# PowerPlane.net
KiCad netlist of a schematic drawn in Altium Designer
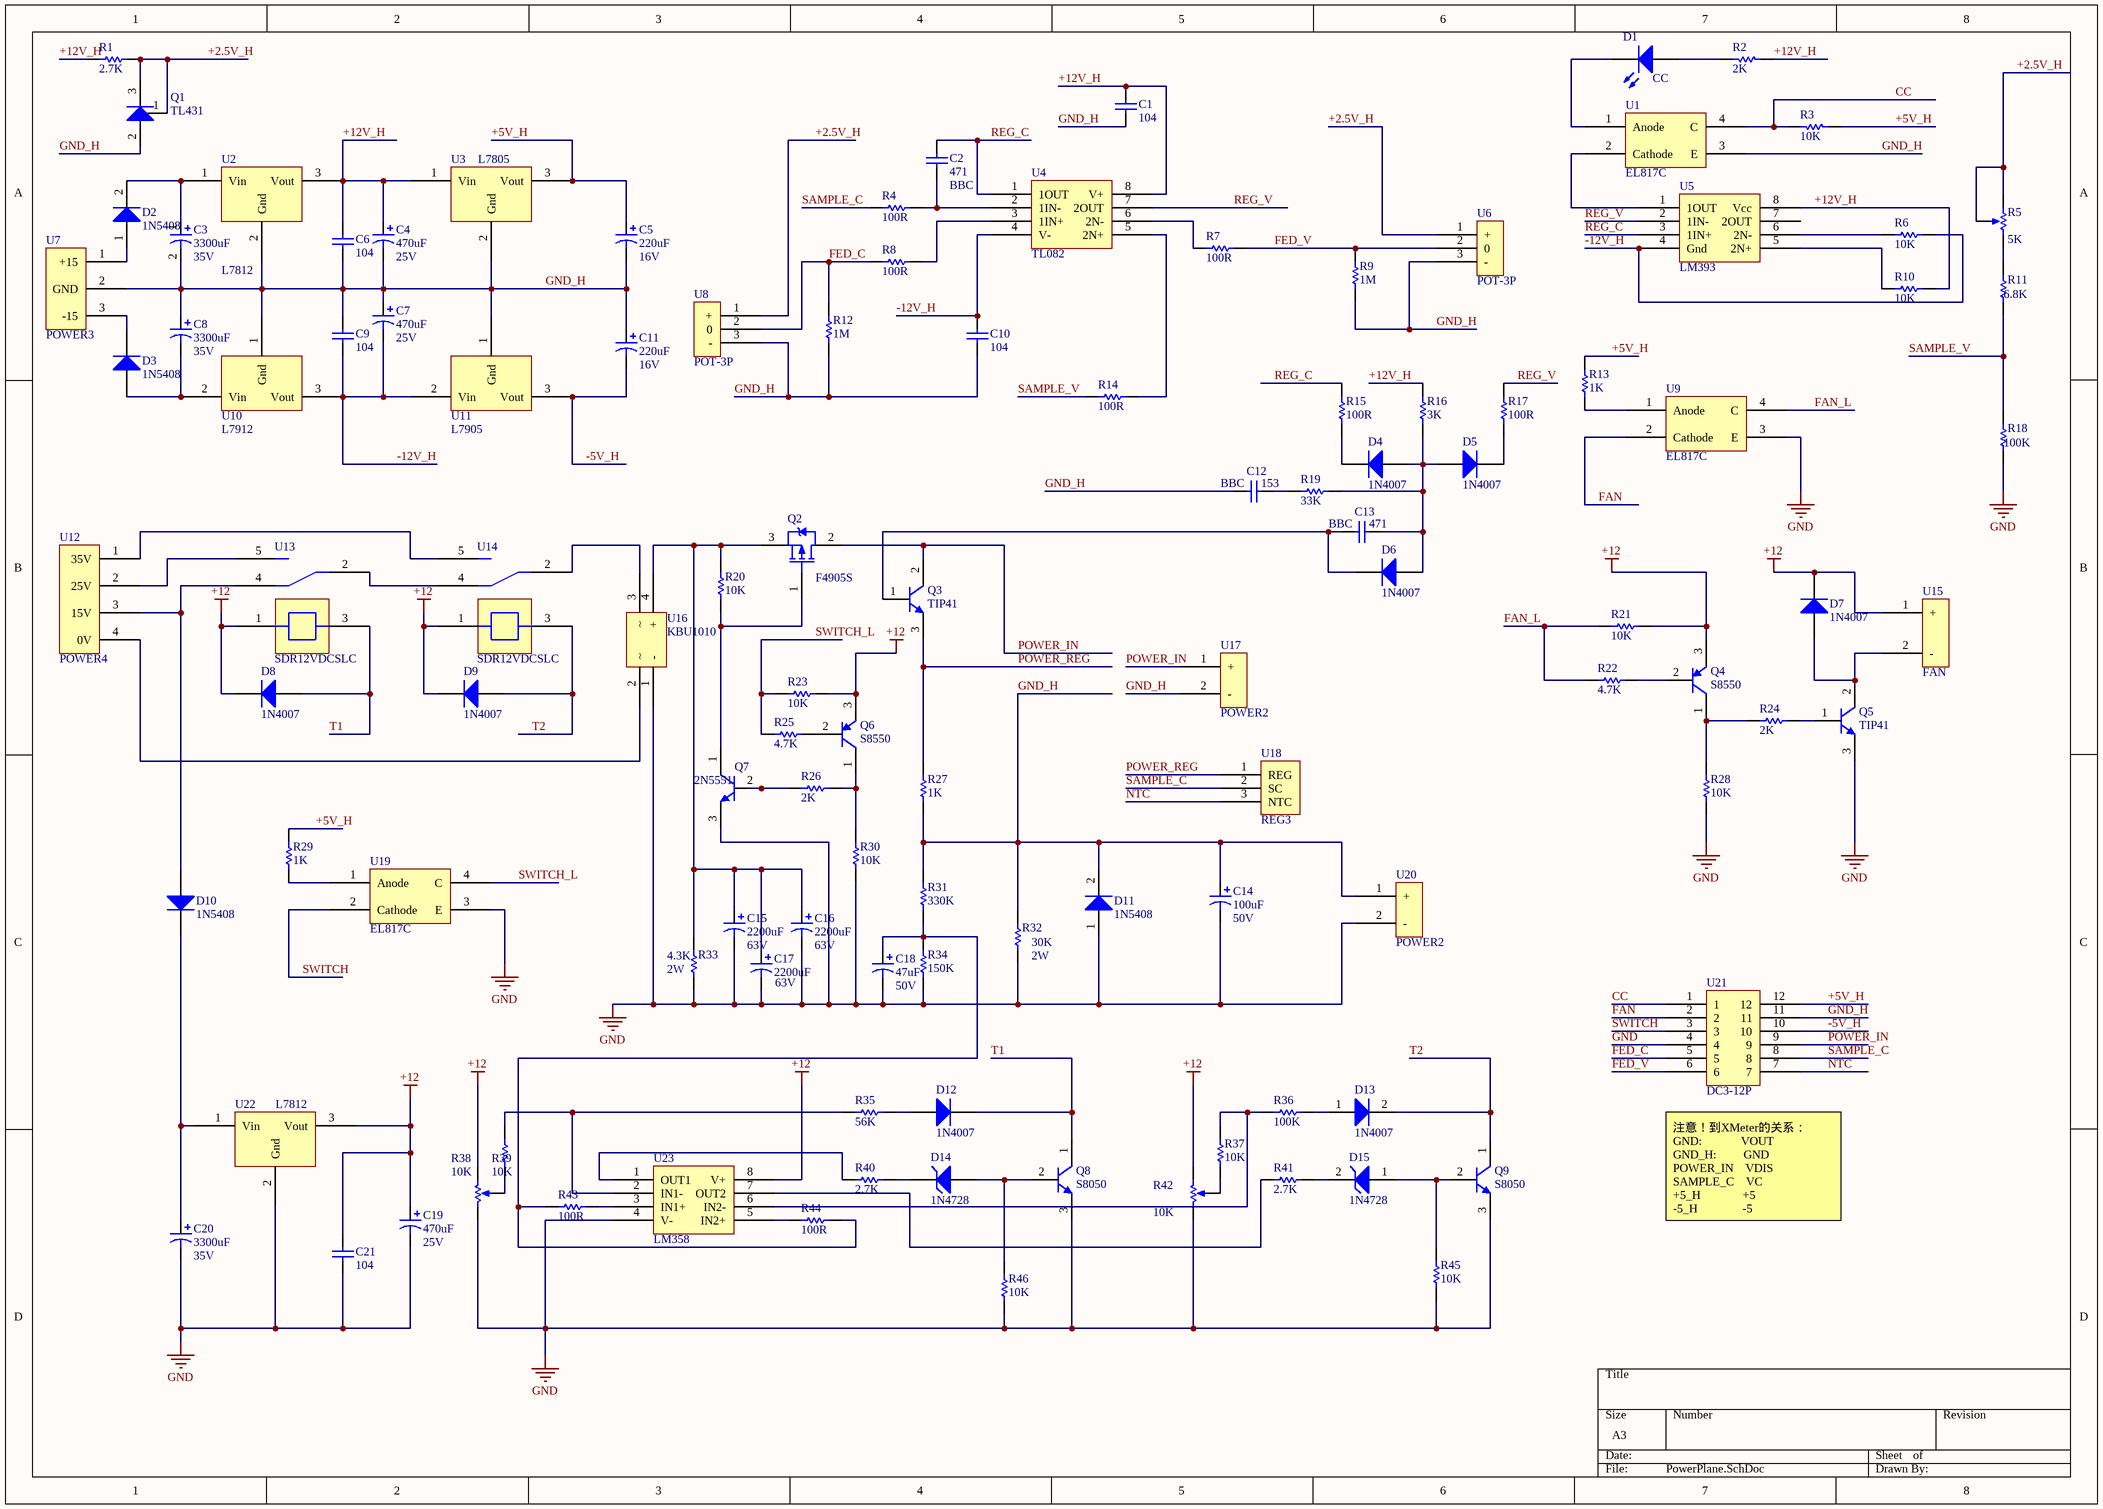
[diagram p0: PowerPlane.SchDoc]

(export (version "E")
  (design (tool "Eeschema 10.0.6"))
  (components
    (comp (ref "C1")
      (value "104")
      (footprint "CNCPowerSupply:RAD-0.2")
      (description "Capacitor")
      (fields (field (name "PUBLISHER") "Altium Limited"))
      (libsource (lib "Miscellaneous Devices") (part "Cap"))
    )
    (comp (ref "C2")
      (value "BBC")
      (footprint "CNCPowerSupply:RAD-0.2")
      (description "Capacitor")
      (fields (field (name "ALTIUM_VALUE") "471") (field (name "PUBLISHER") "Altium Limited"))
      (libsource (lib "Miscellaneous Devices") (part "Cap"))
    )
    (comp (ref "C3")
      (value "35V")
      (footprint "CNCPowerSupply:CAPPR7.5-16x25")
      (description "Polarized Capacitor (Radial)")
      (fields (field (name "ALTIUM_VALUE") "3300uF") (field (name "PUBLISHER") "Altium Limited"))
      (libsource (lib "Miscellaneous Devices") (part "Cap Pol1"))
    )
    (comp (ref "C4")
      (value "25V")
      (footprint "CNCPowerSupply:CAPPR5-8x12")
      (description "Polarized Capacitor (Radial)")
      (fields (field (name "ALTIUM_VALUE") "470uF") (field (name "PUBLISHER") "Altium Limited"))
      (libsource (lib "") (part "Cap Pol1_1"))
    )
    (comp (ref "C5")
      (value "16V")
      (footprint "CNCPowerSupply:CAPPR5-6.3x11")
      (description "Polarized Capacitor (Radial)")
      (fields (field (name "ALTIUM_VALUE") "220uF") (field (name "PUBLISHER") "Altium Limited"))
      (libsource (lib "") (part "Cap Pol1_1"))
    )
    (comp (ref "C6")
      (value "104")
      (footprint "CNCPowerSupply:RAD-0.2")
      (description "Capacitor")
      (fields (field (name "PUBLISHER") "Altium Limited"))
      (libsource (lib "Miscellaneous Devices") (part "Cap"))
    )
    (comp (ref "C7")
      (value "25V")
      (footprint "CNCPowerSupply:CAPPR5-8x12")
      (description "Polarized Capacitor (Radial)")
      (fields (field (name "ALTIUM_VALUE") "470uF") (field (name "PUBLISHER") "Altium Limited"))
      (libsource (lib "") (part "Cap Pol1_1"))
    )
    (comp (ref "C8")
      (value "35V")
      (footprint "CNCPowerSupply:CAPPR7.5-16x25")
      (description "Polarized Capacitor (Radial)")
      (fields (field (name "ALTIUM_VALUE") "3300uF") (field (name "PUBLISHER") "Altium Limited"))
      (libsource (lib "") (part "Cap Pol1_1"))
    )
    (comp (ref "C9")
      (value "104")
      (footprint "CNCPowerSupply:RAD-0.2")
      (description "Capacitor")
      (fields (field (name "PUBLISHER") "Altium Limited"))
      (libsource (lib "Miscellaneous Devices") (part "Cap"))
    )
    (comp (ref "C10")
      (value "104")
      (footprint "CNCPowerSupply:RAD-0.2")
      (description "Capacitor")
      (fields (field (name "PUBLISHER") "Altium Limited"))
      (libsource (lib "Miscellaneous Devices") (part "Cap"))
    )
    (comp (ref "C11")
      (value "16V")
      (footprint "CNCPowerSupply:CAPPR5-6.3x11")
      (description "Polarized Capacitor (Radial)")
      (fields (field (name "ALTIUM_VALUE") "220uF") (field (name "PUBLISHER") "Altium Limited"))
      (libsource (lib "") (part "Cap Pol1_1"))
    )
    (comp (ref "C12")
      (value "BBC")
      (footprint "CNCPowerSupply:RAD-0.4-BBC")
      (description "Capacitor")
      (fields (field (name "ALTIUM_VALUE") "153") (field (name "PUBLISHER") "Altium Limited"))
      (libsource (lib "Miscellaneous Devices") (part "Cap"))
    )
    (comp (ref "C13")
      (value "BBC")
      (footprint "CNCPowerSupply:RAD-0.2")
      (description "Capacitor")
      (fields (field (name "ALTIUM_VALUE") "471") (field (name "PUBLISHER") "Altium Limited"))
      (libsource (lib "Miscellaneous Devices") (part "Cap"))
    )
    (comp (ref "C14")
      (value "50V")
      (footprint "CNCPowerSupply:CAPPR5-8x12")
      (description "Polarized Capacitor (Radial)")
      (fields (field (name "ALTIUM_VALUE") "100uF") (field (name "PUBLISHER") "Altium Limited"))
      (libsource (lib "") (part "Cap Pol1_1"))
    )
    (comp (ref "C15")
      (value "63V")
      (footprint "CNCPowerSupply:CAPPR7.5-18x35.5")
      (description "Polarized Capacitor (Radial)")
      (fields (field (name "ALTIUM_VALUE") "2200uF") (field (name "PUBLISHER") "Altium Limited"))
      (libsource (lib "") (part "Cap Pol1_1"))
    )
    (comp (ref "C16")
      (value "63V")
      (footprint "CNCPowerSupply:CAPPR7.5-18x35.5")
      (description "Polarized Capacitor (Radial)")
      (fields (field (name "ALTIUM_VALUE") "2200uF") (field (name "PUBLISHER") "Altium Limited"))
      (libsource (lib "") (part "Cap Pol1_1"))
    )
    (comp (ref "C17")
      (value "63V")
      (footprint "CNCPowerSupply:CAPPR7.5-18x35.5")
      (description "Polarized Capacitor (Radial)")
      (fields (field (name "ALTIUM_VALUE") "2200uF") (field (name "PUBLISHER") "Altium Limited"))
      (libsource (lib "") (part "Cap Pol1_1"))
    )
    (comp (ref "C18")
      (value "50V")
      (footprint "CNCPowerSupply:CAPPR5-6.3x15")
      (description "Polarized Capacitor (Radial)")
      (fields (field (name "ALTIUM_VALUE") "47uF") (field (name "PUBLISHER") "Altium Limited"))
      (libsource (lib "") (part "Cap Pol1_1"))
    )
    (comp (ref "C19")
      (value "25V")
      (footprint "CNCPowerSupply:CAPPR5-8x12")
      (description "Polarized Capacitor (Radial)")
      (fields (field (name "ALTIUM_VALUE") "470uF") (field (name "PUBLISHER") "Altium Limited"))
      (libsource (lib "") (part "Cap Pol1_1"))
    )
    (comp (ref "C20")
      (value "35V")
      (footprint "CNCPowerSupply:CAPPR7.5-16x25")
      (description "Polarized Capacitor (Radial)")
      (fields (field (name "ALTIUM_VALUE") "3300uF") (field (name "PUBLISHER") "Altium Limited"))
      (libsource (lib "") (part "Cap Pol1_1"))
    )
    (comp (ref "C21")
      (value "104")
      (footprint "CNCPowerSupply:RAD-0.2")
      (description "Capacitor")
      (fields (field (name "PUBLISHER") "Altium Limited"))
      (libsource (lib "Miscellaneous Devices") (part "Cap"))
    )
    (comp (ref "D1")
      (value "CC")
      (footprint "CNCPowerSupply:LED")
      (description "Typical RED GaAs LED")
      (fields (field (name "PUBLISHER") "Altium Limited"))
      (libsource (lib "Miscellaneous Devices") (part "LED1"))
    )
    (comp (ref "D2")
      (value "1N5408")
      (footprint "CNCPowerSupply:DIO18.84-9.6x5.6-Vetical")
      (description "1 Amp General Purpose Rectifier")
      (fields (field (name "PUBLISHER") "Altium Limited"))
      (libsource (lib "Miscellaneous Devices") (part "Diode 1N4007"))
    )
    (comp (ref "D3")
      (value "1N5408")
      (footprint "CNCPowerSupply:DIO18.84-9.6x5.6-Vetical")
      (description "1 Amp General Purpose Rectifier")
      (fields (field (name "PUBLISHER") "Altium Limited"))
      (libsource (lib "") (part "Diode 1N4007_1"))
    )
    (comp (ref "D4")
      (value "1N4007")
      (footprint "CNCPowerSupply:DO-41")
      (description "1 Amp General Purpose Rectifier")
      (fields (field (name "PUBLISHER") "Altium Limited"))
      (libsource (lib "") (part "Diode 1N4007_1"))
    )
    (comp (ref "D5")
      (value "1N4007")
      (footprint "CNCPowerSupply:DO-41")
      (description "1 Amp General Purpose Rectifier")
      (fields (field (name "PUBLISHER") "Altium Limited"))
      (libsource (lib "") (part "Diode 1N4007_1"))
    )
    (comp (ref "D6")
      (value "1N4007")
      (footprint "CNCPowerSupply:DO-41")
      (description "1 Amp General Purpose Rectifier")
      (fields (field (name "PUBLISHER") "Altium Limited"))
      (libsource (lib "") (part "Diode 1N4007_1"))
    )
    (comp (ref "D7")
      (value "1N4007")
      (footprint "CNCPowerSupply:DO-41")
      (description "1 Amp General Purpose Rectifier")
      (fields (field (name "PUBLISHER") "Altium Limited"))
      (libsource (lib "") (part "Diode 1N4007_1"))
    )
    (comp (ref "D8")
      (value "1N4007")
      (footprint "CNCPowerSupply:DO-41")
      (description "1 Amp General Purpose Rectifier")
      (fields (field (name "PUBLISHER") "Altium Limited"))
      (libsource (lib "") (part "Diode 1N4007_1"))
    )
    (comp (ref "D9")
      (value "1N4007")
      (footprint "CNCPowerSupply:DO-41")
      (description "1 Amp General Purpose Rectifier")
      (fields (field (name "PUBLISHER") "Altium Limited"))
      (libsource (lib "") (part "Diode 1N4007_1"))
    )
    (comp (ref "D10")
      (value "1N5408")
      (footprint "CNCPowerSupply:DIO18.84-9.6x5.6-Vetical")
      (description "1 Amp General Purpose Rectifier")
      (fields (field (name "PUBLISHER") "Altium Limited"))
      (libsource (lib "") (part "Diode 1N4007_1"))
    )
    (comp (ref "D11")
      (value "1N5408")
      (footprint "CNCPowerSupply:DIO18.84-9.6x5.6-Vetical")
      (description "1 Amp General Purpose Rectifier")
      (fields (field (name "PUBLISHER") "Altium Limited"))
      (libsource (lib "Miscellaneous Devices") (part "Diode 1N4007"))
    )
    (comp (ref "D12")
      (value "1N4007")
      (footprint "CNCPowerSupply:DO-41")
      (description "1 Amp General Purpose Rectifier")
      (fields (field (name "PUBLISHER") "Altium Limited"))
      (libsource (lib "") (part "Diode 1N4007_1"))
    )
    (comp (ref "D13")
      (value "1N4007")
      (footprint "CNCPowerSupply:DO-41")
      (description "1 Amp General Purpose Rectifier")
      (fields (field (name "PUBLISHER") "Altium Limited"))
      (libsource (lib "Miscellaneous Devices") (part "Diode 1N4007"))
    )
    (comp (ref "D14")
      (value "1N4728")
      (footprint "CNCPowerSupply:DO-41")
      (description "Zener Diode")
      (fields (field (name "PUBLISHER") "Altium Limited"))
      (libsource (lib "") (part "D Zener_1"))
    )
    (comp (ref "D15")
      (value "1N4728")
      (footprint "CNCPowerSupply:DO-41")
      (description "Zener Diode")
      (fields (field (name "PUBLISHER") "Altium Limited"))
      (libsource (lib "Miscellaneous Devices") (part "D Zener"))
    )
    (comp (ref "Q1")
      (value "TL431")
      (footprint "CNCPowerSupply:TO-226-AA")
      (libsource (lib "CNCPowerSupply") (part "TL431"))
    )
    (comp (ref "Q2")
      (value "F4905S")
      (footprint "CNCPowerSupply:D2-PAK")
      (description "P-Channel Power MOSFET")
      (fields (field (name "PUBLISHER") "Altium Limited"))
      (libsource (lib "Miscellaneous Devices") (part "PMOS-2"))
    )
    (comp (ref "Q3")
      (value "TIP41")
      (footprint "CNCPowerSupply:TO-220AB - HEATSINK")
      (description "NPN Bipolar Transistor")
      (fields (field (name "PUBLISHER") "Altium Limited"))
      (libsource (lib "") (part "NPN_1"))
    )
    (comp (ref "Q4")
      (value "S8550")
      (footprint "CNCPowerSupply:TO-92A")
      (description "PNP Bipolar Transistor")
      (fields (field (name "PUBLISHER") "Altium Limited"))
      (libsource (lib "Miscellaneous Devices") (part "PNP"))
    )
    (comp (ref "Q5")
      (value "TIP41")
      (footprint "CNCPowerSupply:TO-220AB")
      (description "NPN Bipolar Transistor")
      (fields (field (name "PUBLISHER") "Altium Limited"))
      (libsource (lib "") (part "NPN_1"))
    )
    (comp (ref "Q6")
      (value "S8550")
      (footprint "CNCPowerSupply:TO-92A")
      (description "PNP Bipolar Transistor")
      (fields (field (name "PUBLISHER") "Altium Limited"))
      (libsource (lib "Miscellaneous Devices") (part "PNP"))
    )
    (comp (ref "Q7")
      (value "2N5551")
      (footprint "CNCPowerSupply:TO-92A")
      (description "NPN Bipolar Transistor")
      (fields (field (name "PUBLISHER") "Altium Limited"))
      (libsource (lib "Miscellaneous Devices") (part "NPN"))
    )
    (comp (ref "Q8")
      (value "S8050")
      (footprint "CNCPowerSupply:TO-92A")
      (description "NPN Bipolar Transistor")
      (fields (field (name "PUBLISHER") "Altium Limited"))
      (libsource (lib "Miscellaneous Devices") (part "NPN"))
    )
    (comp (ref "Q9")
      (value "S8050")
      (footprint "CNCPowerSupply:TO-92A")
      (description "NPN Bipolar Transistor")
      (fields (field (name "PUBLISHER") "Altium Limited"))
      (libsource (lib "Miscellaneous Devices") (part "NPN"))
    )
    (comp (ref "R1")
      (value "2.7K")
      (footprint "CNCPowerSupply:AXIAL-0.3")
      (description "Resistor")
      (fields (field (name "PUBLISHER") "Altium Limited"))
      (libsource (lib "Miscellaneous Devices") (part "Res1"))
    )
    (comp (ref "R2")
      (value "2K")
      (footprint "CNCPowerSupply:AXIAL-0.3")
      (description "Resistor")
      (fields (field (name "PUBLISHER") "Altium Limited"))
      (libsource (lib "Miscellaneous Devices") (part "Res1"))
    )
    (comp (ref "R3")
      (value "10K")
      (footprint "CNCPowerSupply:AXIAL-0.3")
      (description "Resistor")
      (fields (field (name "PUBLISHER") "Altium Limited"))
      (libsource (lib "Miscellaneous Devices") (part "Res1"))
    )
    (comp (ref "R4")
      (value "100R")
      (footprint "CNCPowerSupply:AXIAL-0.3")
      (description "Resistor")
      (fields (field (name "PUBLISHER") "Altium Limited"))
      (libsource (lib "Miscellaneous Devices") (part "Res1"))
    )
    (comp (ref "R5")
      (value "5K")
      (footprint "CNCPowerSupply:VR5")
      (description "Potentiometer")
      (fields (field (name "PUBLISHER") "Altium Limited"))
      (libsource (lib "Miscellaneous Devices") (part "RPot"))
    )
    (comp (ref "R6")
      (value "10K")
      (footprint "CNCPowerSupply:AXIAL-0.3")
      (description "Resistor")
      (fields (field (name "PUBLISHER") "Altium Limited"))
      (libsource (lib "Miscellaneous Devices") (part "Res1"))
    )
    (comp (ref "R7")
      (value "100R")
      (footprint "CNCPowerSupply:AXIAL-0.3")
      (description "Resistor")
      (fields (field (name "PUBLISHER") "Altium Limited"))
      (libsource (lib "Miscellaneous Devices") (part "Res1"))
    )
    (comp (ref "R8")
      (value "100R")
      (footprint "CNCPowerSupply:AXIAL-0.3")
      (description "Resistor")
      (fields (field (name "PUBLISHER") "Altium Limited"))
      (libsource (lib "Miscellaneous Devices") (part "Res1"))
    )
    (comp (ref "R9")
      (value "1M")
      (footprint "CNCPowerSupply:AXIAL-0.3")
      (description "Resistor")
      (fields (field (name "PUBLISHER") "Altium Limited"))
      (libsource (lib "Miscellaneous Devices") (part "Res1"))
    )
    (comp (ref "R10")
      (value "10K")
      (footprint "CNCPowerSupply:AXIAL-0.3")
      (description "Resistor")
      (fields (field (name "PUBLISHER") "Altium Limited"))
      (libsource (lib "Miscellaneous Devices") (part "Res1"))
    )
    (comp (ref "R11")
      (value "6.8K")
      (footprint "CNCPowerSupply:AXIAL-0.3")
      (description "Resistor")
      (fields (field (name "PUBLISHER") "Altium Limited"))
      (libsource (lib "Miscellaneous Devices") (part "Res1"))
    )
    (comp (ref "R12")
      (value "1M")
      (footprint "CNCPowerSupply:AXIAL-0.3")
      (description "Resistor")
      (fields (field (name "PUBLISHER") "Altium Limited"))
      (libsource (lib "Miscellaneous Devices") (part "Res1"))
    )
    (comp (ref "R13")
      (value "1K")
      (footprint "CNCPowerSupply:AXIAL-0.3")
      (description "Resistor")
      (fields (field (name "PUBLISHER") "Altium Limited"))
      (libsource (lib "Miscellaneous Devices") (part "Res1"))
    )
    (comp (ref "R14")
      (value "100R")
      (footprint "CNCPowerSupply:AXIAL-0.3")
      (description "Resistor")
      (fields (field (name "PUBLISHER") "Altium Limited"))
      (libsource (lib "Miscellaneous Devices") (part "Res1"))
    )
    (comp (ref "R15")
      (value "100R")
      (footprint "CNCPowerSupply:AXIAL-0.3")
      (description "Resistor")
      (fields (field (name "PUBLISHER") "Altium Limited"))
      (libsource (lib "Miscellaneous Devices") (part "Res1"))
    )
    (comp (ref "R16")
      (value "3K")
      (footprint "CNCPowerSupply:AXIAL-0.3")
      (description "Resistor")
      (fields (field (name "PUBLISHER") "Altium Limited"))
      (libsource (lib "Miscellaneous Devices") (part "Res1"))
    )
    (comp (ref "R17")
      (value "100R")
      (footprint "CNCPowerSupply:AXIAL-0.3")
      (description "Resistor")
      (fields (field (name "PUBLISHER") "Altium Limited"))
      (libsource (lib "Miscellaneous Devices") (part "Res1"))
    )
    (comp (ref "R18")
      (value "100K")
      (footprint "CNCPowerSupply:AXIAL-0.3")
      (description "Resistor")
      (fields (field (name "PUBLISHER") "Altium Limited"))
      (libsource (lib "Miscellaneous Devices") (part "Res1"))
    )
    (comp (ref "R19")
      (value "33K")
      (footprint "CNCPowerSupply:AXIAL-0.3")
      (description "Resistor")
      (fields (field (name "PUBLISHER") "Altium Limited"))
      (libsource (lib "Miscellaneous Devices") (part "Res1"))
    )
    (comp (ref "R20")
      (value "10K")
      (footprint "CNCPowerSupply:AXIAL-0.3")
      (description "Resistor")
      (fields (field (name "PUBLISHER") "Altium Limited"))
      (libsource (lib "Miscellaneous Devices") (part "Res1"))
    )
    (comp (ref "R21")
      (value "10K")
      (footprint "CNCPowerSupply:AXIAL-0.3")
      (description "Resistor")
      (fields (field (name "PUBLISHER") "Altium Limited"))
      (libsource (lib "Miscellaneous Devices") (part "Res1"))
    )
    (comp (ref "R22")
      (value "4.7K")
      (footprint "CNCPowerSupply:AXIAL-0.3")
      (description "Resistor")
      (fields (field (name "PUBLISHER") "Altium Limited"))
      (libsource (lib "Miscellaneous Devices") (part "Res1"))
    )
    (comp (ref "R23")
      (value "10K")
      (footprint "CNCPowerSupply:AXIAL-0.3")
      (description "Resistor")
      (fields (field (name "PUBLISHER") "Altium Limited"))
      (libsource (lib "Miscellaneous Devices") (part "Res1"))
    )
    (comp (ref "R24")
      (value "2K")
      (footprint "CNCPowerSupply:AXIAL-0.3")
      (description "Resistor")
      (fields (field (name "PUBLISHER") "Altium Limited"))
      (libsource (lib "Miscellaneous Devices") (part "Res1"))
    )
    (comp (ref "R25")
      (value "4.7K")
      (footprint "CNCPowerSupply:AXIAL-0.3")
      (description "Resistor")
      (fields (field (name "PUBLISHER") "Altium Limited"))
      (libsource (lib "Miscellaneous Devices") (part "Res1"))
    )
    (comp (ref "R26")
      (value "2K")
      (footprint "CNCPowerSupply:AXIAL-0.3")
      (description "Resistor")
      (fields (field (name "PUBLISHER") "Altium Limited"))
      (libsource (lib "Miscellaneous Devices") (part "Res1"))
    )
    (comp (ref "R27")
      (value "1K")
      (footprint "CNCPowerSupply:AXIAL-0.3")
      (description "Resistor")
      (fields (field (name "PUBLISHER") "Altium Limited"))
      (libsource (lib "Miscellaneous Devices") (part "Res1"))
    )
    (comp (ref "R28")
      (value "10K")
      (footprint "CNCPowerSupply:AXIAL-0.3")
      (description "Resistor")
      (fields (field (name "PUBLISHER") "Altium Limited"))
      (libsource (lib "Miscellaneous Devices") (part "Res1"))
    )
    (comp (ref "R29")
      (value "1K")
      (footprint "CNCPowerSupply:AXIAL-0.3")
      (description "Resistor")
      (fields (field (name "PUBLISHER") "Altium Limited"))
      (libsource (lib "Miscellaneous Devices") (part "Res1"))
    )
    (comp (ref "R30")
      (value "10K")
      (footprint "CNCPowerSupply:AXIAL-0.3")
      (description "Resistor")
      (fields (field (name "PUBLISHER") "Altium Limited"))
      (libsource (lib "Miscellaneous Devices") (part "Res1"))
    )
    (comp (ref "R31")
      (value "330K")
      (footprint "CNCPowerSupply:AXIAL-0.3")
      (description "Resistor")
      (fields (field (name "PUBLISHER") "Altium Limited"))
      (libsource (lib "Miscellaneous Devices") (part "Res1"))
    )
    (comp (ref "R32")
      (value "2W")
      (footprint "CNCPowerSupply:AXIAL-0.7")
      (description "Resistor")
      (fields (field (name "ALTIUM_VALUE") "30K") (field (name "PUBLISHER") "Altium Limited"))
      (libsource (lib "Miscellaneous Devices") (part "Res1"))
    )
    (comp (ref "R33")
      (value "2W")
      (footprint "CNCPowerSupply:AXIAL-0.7")
      (description "Resistor")
      (fields (field (name "ALTIUM_VALUE") "4.3K") (field (name "PUBLISHER") "Altium Limited"))
      (libsource (lib "Miscellaneous Devices") (part "Res1"))
    )
    (comp (ref "R34")
      (value "150K")
      (footprint "CNCPowerSupply:AXIAL-0.3")
      (description "Resistor")
      (fields (field (name "PUBLISHER") "Altium Limited"))
      (libsource (lib "Miscellaneous Devices") (part "Res1"))
    )
    (comp (ref "R35")
      (value "56K")
      (footprint "CNCPowerSupply:AXIAL-0.3")
      (description "Resistor")
      (fields (field (name "PUBLISHER") "Altium Limited"))
      (libsource (lib "Miscellaneous Devices") (part "Res1"))
    )
    (comp (ref "R36")
      (value "100K")
      (footprint "CNCPowerSupply:AXIAL-0.3")
      (description "Resistor")
      (fields (field (name "PUBLISHER") "Altium Limited"))
      (libsource (lib "Miscellaneous Devices") (part "Res1"))
    )
    (comp (ref "R37")
      (value "10K")
      (footprint "CNCPowerSupply:AXIAL-0.3")
      (description "Resistor")
      (fields (field (name "PUBLISHER") "Altium Limited"))
      (libsource (lib "Miscellaneous Devices") (part "Res1"))
    )
    (comp (ref "R38")
      (value "10K")
      (footprint "CNCPowerSupply:VR5")
      (description "Potentiometer")
      (fields (field (name "PUBLISHER") "Altium Limited"))
      (libsource (lib "Miscellaneous Devices") (part "RPot"))
    )
    (comp (ref "R39")
      (value "10K")
      (footprint "CNCPowerSupply:AXIAL-0.3")
      (description "Resistor")
      (fields (field (name "PUBLISHER") "Altium Limited"))
      (libsource (lib "Miscellaneous Devices") (part "Res1"))
    )
    (comp (ref "R40")
      (value "2.7K")
      (footprint "CNCPowerSupply:AXIAL-0.3")
      (description "Resistor")
      (fields (field (name "PUBLISHER") "Altium Limited"))
      (libsource (lib "Miscellaneous Devices") (part "Res1"))
    )
    (comp (ref "R41")
      (value "2.7K")
      (footprint "CNCPowerSupply:AXIAL-0.3")
      (description "Resistor")
      (fields (field (name "PUBLISHER") "Altium Limited"))
      (libsource (lib "Miscellaneous Devices") (part "Res1"))
    )
    (comp (ref "R42")
      (value "10K")
      (footprint "CNCPowerSupply:VR5")
      (description "Potentiometer")
      (fields (field (name "PUBLISHER") "Altium Limited"))
      (libsource (lib "Miscellaneous Devices") (part "RPot"))
    )
    (comp (ref "R43")
      (value "100R")
      (footprint "CNCPowerSupply:AXIAL-0.3")
      (description "Resistor")
      (fields (field (name "PUBLISHER") "Altium Limited"))
      (libsource (lib "Miscellaneous Devices") (part "Res1"))
    )
    (comp (ref "R44")
      (value "100R")
      (footprint "CNCPowerSupply:AXIAL-0.3")
      (description "Resistor")
      (fields (field (name "PUBLISHER") "Altium Limited"))
      (libsource (lib "Miscellaneous Devices") (part "Res1"))
    )
    (comp (ref "R45")
      (value "10K")
      (footprint "CNCPowerSupply:AXIAL-0.3")
      (description "Resistor")
      (fields (field (name "PUBLISHER") "Altium Limited"))
      (libsource (lib "Miscellaneous Devices") (part "Res1"))
    )
    (comp (ref "R46")
      (value "10K")
      (footprint "CNCPowerSupply:AXIAL-0.3")
      (description "Resistor")
      (fields (field (name "PUBLISHER") "Altium Limited"))
      (libsource (lib "Miscellaneous Devices") (part "Res1"))
    )
    (comp (ref "U1")
      (value "EL817C")
      (footprint "CNCPowerSupply:PC817")
      (libsource (lib "CNCPowerSupply") (part "EL817C"))
    )
    (comp (ref "U2")
      (value "L7812")
      (footprint "CNCPowerSupply:TO-220AB - HEATSINK")
      (libsource (lib "CNCPowerSupply") (part "L7812"))
    )
    (comp (ref "U3")
      (value "L7805")
      (footprint "CNCPowerSupply:TO-220AB - HEATSINK")
      (libsource (lib "CNCPowerSupply") (part "L7805"))
    )
    (comp (ref "U4")
      (value "TL082")
      (footprint "CNCPowerSupply:DIP-8")
      (libsource (lib "CNCPowerSupply") (part "TL082"))
    )
    (comp (ref "U5")
      (value "LM393")
      (footprint "CNCPowerSupply:DIP-8")
      (libsource (lib "CNCPowerSupply") (part "LM393"))
    )
    (comp (ref "U6")
      (value "POT-3P")
      (footprint "CNCPowerSupply:X254-3P")
      (libsource (lib "CNCPowerSupply") (part "POT-3P"))
    )
    (comp (ref "U7")
      (value "POWER3")
      (footprint "CNCPowerSupply:KF128-50-3P")
      (description "Power Connector 3")
      (libsource (lib "CNCPowerSupply") (part "POWER3"))
    )
    (comp (ref "U8")
      (value "POT-3P")
      (footprint "CNCPowerSupply:X254-3P")
      (libsource (lib "") (part "POT-3P_1"))
    )
    (comp (ref "U9")
      (value "EL817C")
      (footprint "CNCPowerSupply:PC817")
      (libsource (lib "CNCPowerSupply") (part "EL817C"))
    )
    (comp (ref "U10")
      (value "L7912")
      (footprint "CNCPowerSupply:TO-220AB - HEATSINK")
      (libsource (lib "CNCPowerSupply") (part "L7912"))
    )
    (comp (ref "U11")
      (value "L7905")
      (footprint "CNCPowerSupply:TO-220AB - HEATSINK")
      (libsource (lib "CNCPowerSupply") (part "L7905"))
    )
    (comp (ref "U12")
      (value "POWER4")
      (footprint "CNCPowerSupply:KF128-50-4P")
      (description "Power Connector 3")
      (libsource (lib "CNCPowerSupply") (part "POWER4"))
    )
    (comp (ref "U13")
      (value "SDR12VDCSLC")
      (footprint "CNCPowerSupply:SDR12VDCSLC")
      (libsource (lib "CNCPowerSupply") (part "SDR12VDCSLC"))
    )
    (comp (ref "U14")
      (value "SDR12VDCSLC")
      (footprint "CNCPowerSupply:SDR12VDCSLC")
      (libsource (lib "CNCPowerSupply") (part "SDR12VDCSLC"))
    )
    (comp (ref "U15")
      (value "FAN")
      (footprint "CNCPowerSupply:X254-2P")
      (libsource (lib "CNCPowerSupply") (part "FAN"))
    )
    (comp (ref "U16")
      (value "KBU1010")
      (footprint "CNCPowerSupply:KBU1010")
      (libsource (lib "CNCPowerSupply") (part "KBU1010"))
    )
    (comp (ref "U17")
      (value "POWER2")
      (footprint "CNCPowerSupply:KF128-50-2P")
      (libsource (lib "CNCPowerSupply") (part "POWER2"))
    )
    (comp (ref "U18")
      (value "REG3")
      (footprint "CNCPowerSupply:X254-3P")
      (description "REG2")
      (libsource (lib "CNCPowerSupply") (part "REG3"))
    )
    (comp (ref "U19")
      (value "EL817C")
      (footprint "CNCPowerSupply:PC817")
      (libsource (lib "CNCPowerSupply") (part "EL817C"))
    )
    (comp (ref "U20")
      (value "POWER2")
      (footprint "CNCPowerSupply:KF128-50-2P")
      (libsource (lib "CNCPowerSupply") (part "POWER2"))
    )
    (comp (ref "U21")
      (value "DC3-12P")
      (footprint "CNCPowerSupply:DC3-12P")
      (libsource (lib "CNCPowerSupply") (part "DC3-12P"))
    )
    (comp (ref "U22")
      (value "L7812")
      (footprint "CNCPowerSupply:TO-220AB - HEATSINK")
      (libsource (lib "CNCPowerSupply") (part "L7812"))
    )
    (comp (ref "U23")
      (value "LM358")
      (footprint "CNCPowerSupply:DIP-8")
      (libsource (lib "CNCPowerSupply") (part "LM358"))
    )
  )
  (nets
    (net (code "1") (name "+12") (class "Default")
      (node (ref "C19") (pin "1") (pinfunction "1_1") (pintype "passive"))
      (node (ref "C21") (pin "2") (pinfunction "2_2") (pintype "passive"))
      (node (ref "D7") (pin "2") (pinfunction "K_2") (pintype "passive"))
      (node (ref "D8") (pin "2") (pinfunction "K_2") (pintype "passive"))
      (node (ref "D9") (pin "2") (pinfunction "K_2") (pintype "passive"))
      (node (ref "Q4") (pin "3") (pinfunction "E_3") (pintype "passive"))
      (node (ref "Q6") (pin "3") (pinfunction "E_3") (pintype "passive"))
      (node (ref "R21") (pin "2") (pinfunction "2_2") (pintype "passive"))
      (node (ref "R23") (pin "2") (pinfunction "2_2") (pintype "passive"))
      (node (ref "R38") (pin "1") (pinfunction "TOP_1") (pintype "passive"))
      (node (ref "R42") (pin "1") (pinfunction "TOP_1") (pintype "passive"))
      (node (ref "U13") (pin "1") (pinfunction "V+_1") (pintype "passive"))
      (node (ref "U14") (pin "1") (pinfunction "V+_1") (pintype "passive"))
      (node (ref "U15") (pin "1") (pinfunction "+_1") (pintype "passive"))
      (node (ref "U22") (pin "3") (pinfunction "Vout_3") (pintype "passive"))
      (node (ref "U23") (pin "8") (pinfunction "V+_8") (pintype "passive"))
    )
    (net (code "2") (name "/+2.5V_H") (class "Default")
      (node (ref "Q1") (pin "1") (pinfunction "REF_1") (pintype "passive"))
      (node (ref "Q1") (pin "3") (pinfunction "K_3") (pintype "passive"))
      (node (ref "R1") (pin "2") (pinfunction "2_2") (pintype "passive"))
      (node (ref "R5") (pin "1") (pinfunction "TOP_1") (pintype "passive"))
      (node (ref "R5") (pin "3") (pinfunction "TAP_3") (pintype "passive"))
      (node (ref "U6") (pin "1") (pinfunction "+_1") (pintype "passive"))
      (node (ref "U8") (pin "1") (pinfunction "+_1") (pintype "passive"))
    )
    (net (code "3") (name "/+5V_H") (class "Default")
      (node (ref "C5") (pin "1") (pinfunction "1_1") (pintype "passive"))
      (node (ref "R13") (pin "1") (pinfunction "1_1") (pintype "passive"))
      (node (ref "R29") (pin "1") (pinfunction "1_1") (pintype "passive"))
      (node (ref "R3") (pin "1") (pinfunction "1_1") (pintype "passive"))
      (node (ref "U21") (pin "12") (pinfunction "12_12") (pintype "passive"))
      (node (ref "U3") (pin "3") (pinfunction "Vout_3") (pintype "passive"))
    )
    (net (code "4") (name "/+12V_H") (class "Default")
      (node (ref "C1") (pin "2") (pinfunction "2_2") (pintype "passive"))
      (node (ref "C4") (pin "1") (pinfunction "1_1") (pintype "passive"))
      (node (ref "C6") (pin "2") (pinfunction "2_2") (pintype "passive"))
      (node (ref "R1") (pin "1") (pinfunction "1_1") (pintype "passive"))
      (node (ref "R10") (pin "2") (pinfunction "2_2") (pintype "passive"))
      (node (ref "R16") (pin "1") (pinfunction "1_1") (pintype "passive"))
      (node (ref "R2") (pin "1") (pinfunction "1_1") (pintype "passive"))
      (node (ref "U2") (pin "3") (pinfunction "Vout_3") (pintype "passive"))
      (node (ref "U3") (pin "1") (pinfunction "Vin_1") (pintype "passive"))
      (node (ref "U4") (pin "8") (pinfunction "V+_8") (pintype "passive"))
      (node (ref "U5") (pin "8") (pinfunction "Vcc_8") (pintype "passive"))
    )
    (net (code "5") (name "/-5V_H") (class "Default")
      (node (ref "C11") (pin "2") (pinfunction "2_2") (pintype "passive"))
      (node (ref "U11") (pin "3") (pinfunction "Vout_3") (pintype "passive"))
      (node (ref "U21") (pin "10") (pinfunction "10_10") (pintype "passive"))
    )
    (net (code "6") (name "/-12V_H") (class "Default")
      (node (ref "C10") (pin "2") (pinfunction "2_2") (pintype "passive"))
      (node (ref "C7") (pin "2") (pinfunction "2_2") (pintype "passive"))
      (node (ref "C9") (pin "1") (pinfunction "1_1") (pintype "passive"))
      (node (ref "R6") (pin "2") (pinfunction "2_2") (pintype "passive"))
      (node (ref "U10") (pin "3") (pinfunction "Vout_3") (pintype "passive"))
      (node (ref "U11") (pin "2") (pinfunction "Vin_2") (pintype "passive"))
      (node (ref "U4") (pin "4") (pinfunction "V-_4") (pintype "passive"))
      (node (ref "U5") (pin "4") (pinfunction "Gnd_4") (pintype "passive"))
    )
    (net (code "7") (name "/CC") (class "Default")
      (node (ref "R3") (pin "2") (pinfunction "2_2") (pintype "passive"))
      (node (ref "U1") (pin "4") (pinfunction "C_4") (pintype "passive"))
      (node (ref "U21") (pin "1") (pinfunction "1_1") (pintype "passive"))
    )
    (net (code "8") (name "/FAN") (class "Default")
      (node (ref "U21") (pin "2") (pinfunction "2_2") (pintype "passive"))
      (node (ref "U9") (pin "2") (pinfunction "Cathode_2") (pintype "passive"))
    )
    (net (code "9") (name "/FAN_L") (class "Default")
      (node (ref "R21") (pin "1") (pinfunction "1_1") (pintype "passive"))
      (node (ref "R22") (pin "1") (pinfunction "1_1") (pintype "passive"))
      (node (ref "U9") (pin "4") (pinfunction "C_4") (pintype "passive"))
    )
    (net (code "10") (name "/FED_C") (class "Default")
      (node (ref "R12") (pin "1") (pinfunction "1_1") (pintype "passive"))
      (node (ref "R8") (pin "2") (pinfunction "2_2") (pintype "passive"))
      (node (ref "U21") (pin "5") (pinfunction "5_5") (pintype "passive"))
      (node (ref "U8") (pin "2") (pinfunction "0_2") (pintype "passive"))
    )
    (net (code "11") (name "/FED_V") (class "Default")
      (node (ref "R7") (pin "1") (pinfunction "1_1") (pintype "passive"))
      (node (ref "R9") (pin "1") (pinfunction "1_1") (pintype "passive"))
      (node (ref "U21") (pin "6") (pinfunction "6_6") (pintype "passive"))
      (node (ref "U6") (pin "2") (pinfunction "0_2") (pintype "passive"))
    )
    (net (code "12") (name "/GND_H") (class "Default")
      (node (ref "C1") (pin "1") (pinfunction "1_1") (pintype "passive"))
      (node (ref "C10") (pin "1") (pinfunction "1_1") (pintype "passive"))
      (node (ref "C11") (pin "1") (pinfunction "1_1") (pintype "passive"))
      (node (ref "C12") (pin "2") (pinfunction "2_2") (pintype "passive"))
      (node (ref "C14") (pin "1") (pinfunction "1_1") (pintype "passive"))
      (node (ref "C3") (pin "2") (pinfunction "2_2") (pintype "passive"))
      (node (ref "C4") (pin "2") (pinfunction "2_2") (pintype "passive"))
      (node (ref "C5") (pin "2") (pinfunction "2_2") (pintype "passive"))
      (node (ref "C6") (pin "1") (pinfunction "1_1") (pintype "passive"))
      (node (ref "C7") (pin "1") (pinfunction "1_1") (pintype "passive"))
      (node (ref "C8") (pin "1") (pinfunction "1_1") (pintype "passive"))
      (node (ref "C9") (pin "2") (pinfunction "2_2") (pintype "passive"))
      (node (ref "D11") (pin "2") (pinfunction "K_2") (pintype "passive"))
      (node (ref "Q1") (pin "2") (pinfunction "A_2") (pintype "passive"))
      (node (ref "R12") (pin "2") (pinfunction "2_2") (pintype "passive"))
      (node (ref "R27") (pin "1") (pinfunction "1_1") (pintype "passive"))
      (node (ref "R31") (pin "2") (pinfunction "2_2") (pintype "passive"))
      (node (ref "R32") (pin "2") (pinfunction "2_2") (pintype "passive"))
      (node (ref "R9") (pin "2") (pinfunction "2_2") (pintype "passive"))
      (node (ref "U1") (pin "3") (pinfunction "E_3") (pintype "passive"))
      (node (ref "U10") (pin "1") (pinfunction "Gnd_1") (pintype "passive"))
      (node (ref "U11") (pin "1") (pinfunction "Gnd_1") (pintype "passive"))
      (node (ref "U17") (pin "2") (pinfunction "-_2") (pintype "passive"))
      (node (ref "U2") (pin "2") (pinfunction "Gnd_2") (pintype "passive"))
      (node (ref "U20") (pin "1") (pinfunction "+_1") (pintype "passive"))
      (node (ref "U21") (pin "11") (pinfunction "11_11") (pintype "passive"))
      (node (ref "U3") (pin "2") (pinfunction "Gnd_2") (pintype "passive"))
      (node (ref "U6") (pin "3") (pinfunction "-_3") (pintype "passive"))
      (node (ref "U7") (pin "2") (pinfunction "GND_2") (pintype "passive"))
      (node (ref "U8") (pin "3") (pinfunction "-_3") (pintype "passive"))
    )
    (net (code "13") (name "/NTC") (class "Default")
      (node (ref "U18") (pin "3") (pinfunction "NTC_3") (pintype "passive"))
      (node (ref "U21") (pin "7") (pinfunction "7_7") (pintype "passive"))
    )
    (net (code "14") (name "/POWER_IN") (class "Default")
      (node (ref "Q2") (pin "2") (pinfunction "D_2") (pintype "passive"))
      (node (ref "Q3") (pin "2") (pinfunction "C_2") (pintype "passive"))
      (node (ref "U17") (pin "1") (pinfunction "+_1") (pintype "passive"))
      (node (ref "U21") (pin "9") (pinfunction "9_9") (pintype "passive"))
    )
    (net (code "15") (name "/POWER_REG") (class "Default")
      (node (ref "Q3") (pin "3") (pinfunction "E_3") (pintype "passive"))
      (node (ref "R27") (pin "2") (pinfunction "2_2") (pintype "passive"))
      (node (ref "U18") (pin "1") (pinfunction "REG_1") (pintype "passive"))
    )
    (net (code "16") (name "/REG_C") (class "Default")
      (node (ref "C2") (pin "1") (pinfunction "1_1") (pintype "passive"))
      (node (ref "R15") (pin "1") (pinfunction "1_1") (pintype "passive"))
      (node (ref "U4") (pin "1") (pinfunction "1OUT_1") (pintype "passive"))
      (node (ref "U5") (pin "3") (pinfunction "1IN+_3") (pintype "passive"))
    )
    (net (code "17") (name "/REG_V") (class "Default")
      (node (ref "R17") (pin "1") (pinfunction "1_1") (pintype "passive"))
      (node (ref "U4") (pin "7") (pinfunction "2OUT_7") (pintype "passive"))
      (node (ref "U5") (pin "2") (pinfunction "1IN-_2") (pintype "passive"))
    )
    (net (code "18") (name "/SAMPLE_C") (class "Default")
      (node (ref "R4") (pin "2") (pinfunction "2_2") (pintype "passive"))
      (node (ref "U18") (pin "2") (pinfunction "SC_2") (pintype "passive"))
      (node (ref "U21") (pin "8") (pinfunction "8_8") (pintype "passive"))
    )
    (net (code "19") (name "/SAMPLE_V") (class "Default")
      (node (ref "R11") (pin "2") (pinfunction "2_2") (pintype "passive"))
      (node (ref "R14") (pin "2") (pinfunction "2_2") (pintype "passive"))
      (node (ref "R18") (pin "1") (pinfunction "1_1") (pintype "passive"))
    )
    (net (code "20") (name "/SWITCH") (class "Default")
      (node (ref "U19") (pin "2") (pinfunction "Cathode_2") (pintype "passive"))
      (node (ref "U21") (pin "3") (pinfunction "3_3") (pintype "passive"))
    )
    (net (code "21") (name "/SWITCH_L") (class "Default")
      (node (ref "R23") (pin "1") (pinfunction "1_1") (pintype "passive"))
      (node (ref "R25") (pin "1") (pinfunction "1_1") (pintype "passive"))
      (node (ref "U19") (pin "4") (pinfunction "C_4") (pintype "passive"))
    )
    (net (code "22") (name "/T1") (class "Default")
      (node (ref "D12") (pin "2") (pinfunction "K_2") (pintype "passive"))
      (node (ref "D8") (pin "1") (pinfunction "A_1") (pintype "passive"))
      (node (ref "Q8") (pin "1") (pinfunction "C_1") (pintype "passive"))
      (node (ref "U13") (pin "3") (pinfunction "V-_3") (pintype "passive"))
    )
    (net (code "23") (name "/T2") (class "Default")
      (node (ref "D13") (pin "2") (pinfunction "K_2") (pintype "passive"))
      (node (ref "D9") (pin "1") (pinfunction "A_1") (pintype "passive"))
      (node (ref "Q9") (pin "1") (pinfunction "C_1") (pintype "passive"))
      (node (ref "U14") (pin "3") (pinfunction "V-_3") (pintype "passive"))
    )
    (net (code "24") (name "GND") (class "Default")
      (node (ref "C14") (pin "2") (pinfunction "2_2") (pintype "passive"))
      (node (ref "C15") (pin "2") (pinfunction "2_2") (pintype "passive"))
      (node (ref "C16") (pin "2") (pinfunction "2_2") (pintype "passive"))
      (node (ref "C17") (pin "2") (pinfunction "2_2") (pintype "passive"))
      (node (ref "C18") (pin "2") (pinfunction "2_2") (pintype "passive"))
      (node (ref "C19") (pin "2") (pinfunction "2_2") (pintype "passive"))
      (node (ref "C20") (pin "2") (pinfunction "2_2") (pintype "passive"))
      (node (ref "C21") (pin "1") (pinfunction "1_1") (pintype "passive"))
      (node (ref "D11") (pin "1") (pinfunction "A_1") (pintype "passive"))
      (node (ref "Q5") (pin "3") (pinfunction "E_3") (pintype "passive"))
      (node (ref "Q7") (pin "3") (pinfunction "E_3") (pintype "passive"))
      (node (ref "Q8") (pin "3") (pinfunction "E_3") (pintype "passive"))
      (node (ref "Q9") (pin "3") (pinfunction "E_3") (pintype "passive"))
      (node (ref "R18") (pin "2") (pinfunction "2_2") (pintype "passive"))
      (node (ref "R28") (pin "2") (pinfunction "2_2") (pintype "passive"))
      (node (ref "R30") (pin "2") (pinfunction "2_2") (pintype "passive"))
      (node (ref "R32") (pin "1") (pinfunction "1_1") (pintype "passive"))
      (node (ref "R33") (pin "1") (pinfunction "1_1") (pintype "passive"))
      (node (ref "R34") (pin "1") (pinfunction "1_1") (pintype "passive"))
      (node (ref "R38") (pin "2") (pinfunction "BOT_2") (pintype "passive"))
      (node (ref "R42") (pin "2") (pinfunction "BOT_2") (pintype "passive"))
      (node (ref "R45") (pin "2") (pinfunction "2_2") (pintype "passive"))
      (node (ref "R46") (pin "2") (pinfunction "2_2") (pintype "passive"))
      (node (ref "U16") (pin "1") (pinfunction "-_1") (pintype "passive"))
      (node (ref "U19") (pin "3") (pinfunction "E_3") (pintype "passive"))
      (node (ref "U20") (pin "2") (pinfunction "-_2") (pintype "passive"))
      (node (ref "U21") (pin "4") (pinfunction "4_4") (pintype "passive"))
      (node (ref "U22") (pin "2") (pinfunction "Gnd_2") (pintype "passive"))
      (node (ref "U23") (pin "4") (pinfunction "V-_4") (pintype "passive"))
      (node (ref "U9") (pin "3") (pinfunction "E_3") (pintype "passive"))
    )
    (net (code "25") (name "Net-(C12-Pad1)") (class "Default")
      (node (ref "C12") (pin "1") (pinfunction "1_1") (pintype "passive"))
      (node (ref "R19") (pin "2") (pinfunction "2_2") (pintype "passive"))
    )
    (net (code "26") (name "Net-(C18-Pad1)") (class "Default")
      (node (ref "C18") (pin "1") (pinfunction "1_1") (pintype "passive"))
      (node (ref "R31") (pin "1") (pinfunction "1_1") (pintype "passive"))
      (node (ref "R34") (pin "2") (pinfunction "2_2") (pintype "passive"))
      (node (ref "R43") (pin "2") (pinfunction "2_2") (pintype "passive"))
      (node (ref "R44") (pin "1") (pinfunction "1_1") (pintype "passive"))
    )
    (net (code "27") (name "Net-(D1-A)") (class "Default")
      (node (ref "D1") (pin "1") (pinfunction "A_1") (pintype "passive"))
      (node (ref "R2") (pin "2") (pinfunction "2_2") (pintype "passive"))
    )
    (net (code "28") (name "Net-(D1-K)") (class "Default")
      (node (ref "D1") (pin "2") (pinfunction "K_2") (pintype "passive"))
      (node (ref "U1") (pin "1") (pinfunction "Anode_1") (pintype "passive"))
    )
    (net (code "29") (name "Net-(D2-A)") (class "Default")
      (node (ref "D2") (pin "1") (pinfunction "A_1") (pintype "passive"))
      (node (ref "U7") (pin "1") (pinfunction "+15_1") (pintype "passive"))
    )
    (net (code "30") (name "Net-(D2-K)") (class "Default")
      (node (ref "C3") (pin "1") (pinfunction "1_1") (pintype "passive"))
      (node (ref "D2") (pin "2") (pinfunction "K_2") (pintype "passive"))
      (node (ref "U2") (pin "1") (pinfunction "Vin_1") (pintype "passive"))
    )
    (net (code "31") (name "Net-(D3-A)") (class "Default")
      (node (ref "C8") (pin "2") (pinfunction "2_2") (pintype "passive"))
      (node (ref "D3") (pin "1") (pinfunction "A_1") (pintype "passive"))
      (node (ref "U10") (pin "2") (pinfunction "Vin_2") (pintype "passive"))
    )
    (net (code "32") (name "Net-(D3-K)") (class "Default")
      (node (ref "D3") (pin "2") (pinfunction "K_2") (pintype "passive"))
      (node (ref "U7") (pin "3") (pinfunction "-15_3") (pintype "passive"))
    )
    (net (code "33") (name "Net-(D4-A)") (class "Default")
      (node (ref "C13") (pin "1") (pinfunction "1_1") (pintype "passive"))
      (node (ref "D4") (pin "1") (pinfunction "A_1") (pintype "passive"))
      (node (ref "D5") (pin "1") (pinfunction "A_1") (pintype "passive"))
      (node (ref "D6") (pin "1") (pinfunction "A_1") (pintype "passive"))
      (node (ref "R16") (pin "2") (pinfunction "2_2") (pintype "passive"))
      (node (ref "R19") (pin "1") (pinfunction "1_1") (pintype "passive"))
    )
    (net (code "34") (name "Net-(D4-K)") (class "Default")
      (node (ref "D4") (pin "2") (pinfunction "K_2") (pintype "passive"))
      (node (ref "R15") (pin "2") (pinfunction "2_2") (pintype "passive"))
    )
    (net (code "35") (name "Net-(D5-K)") (class "Default")
      (node (ref "D5") (pin "2") (pinfunction "K_2") (pintype "passive"))
      (node (ref "R17") (pin "2") (pinfunction "2_2") (pintype "passive"))
    )
    (net (code "36") (name "Net-(D6-K)") (class "Default")
      (node (ref "C13") (pin "2") (pinfunction "2_2") (pintype "passive"))
      (node (ref "D6") (pin "2") (pinfunction "K_2") (pintype "passive"))
      (node (ref "Q3") (pin "1") (pinfunction "B_1") (pintype "passive"))
    )
    (net (code "37") (name "Net-(D7-A)") (class "Default")
      (node (ref "D7") (pin "1") (pinfunction "A_1") (pintype "passive"))
      (node (ref "Q5") (pin "2") (pinfunction "C_2") (pintype "passive"))
      (node (ref "U15") (pin "2") (pinfunction "-_2") (pintype "passive"))
    )
    (net (code "38") (name "Net-(D10-A)") (class "Default")
      (node (ref "D10") (pin "1") (pinfunction "A_1") (pintype "passive"))
      (node (ref "U12") (pin "3") (pinfunction "15V_3") (pintype "passive"))
      (node (ref "U13") (pin "4") (pinfunction "I_4") (pintype "passive"))
    )
    (net (code "39") (name "Net-(D10-K)") (class "Default")
      (node (ref "C20") (pin "1") (pinfunction "1_1") (pintype "passive"))
      (node (ref "D10") (pin "2") (pinfunction "K_2") (pintype "passive"))
      (node (ref "U22") (pin "1") (pinfunction "Vin_1") (pintype "passive"))
    )
    (net (code "40") (name "Net-(D12-A)") (class "Default")
      (node (ref "D12") (pin "1") (pinfunction "A_1") (pintype "passive"))
      (node (ref "R35") (pin "1") (pinfunction "1_1") (pintype "passive"))
    )
    (net (code "41") (name "Net-(D13-A)") (class "Default")
      (node (ref "D13") (pin "1") (pinfunction "A_1") (pintype "passive"))
      (node (ref "R36") (pin "1") (pinfunction "1_1") (pintype "passive"))
    )
    (net (code "42") (name "Net-(D14-A)") (class "Default")
      (node (ref "D14") (pin "1") (pinfunction "A_1") (pintype "passive"))
      (node (ref "Q8") (pin "2") (pinfunction "B_2") (pintype "passive"))
      (node (ref "R46") (pin "1") (pinfunction "1_1") (pintype "passive"))
    )
    (net (code "43") (name "Net-(D14-K)") (class "Default")
      (node (ref "D14") (pin "2") (pinfunction "K_2") (pintype "passive"))
      (node (ref "R40") (pin "1") (pinfunction "1_1") (pintype "passive"))
    )
    (net (code "44") (name "Net-(D15-A)") (class "Default")
      (node (ref "D15") (pin "1") (pinfunction "A_1") (pintype "passive"))
      (node (ref "Q9") (pin "2") (pinfunction "B_2") (pintype "passive"))
      (node (ref "R45") (pin "1") (pinfunction "1_1") (pintype "passive"))
    )
    (net (code "45") (name "Net-(D15-K)") (class "Default")
      (node (ref "D15") (pin "2") (pinfunction "K_2") (pintype "passive"))
      (node (ref "R41") (pin "1") (pinfunction "1_1") (pintype "passive"))
    )
    (net (code "46") (name "Net-(Q2-G)") (class "Default")
      (node (ref "Q2") (pin "1") (pinfunction "G_1") (pintype "passive"))
      (node (ref "Q7") (pin "1") (pinfunction "C_1") (pintype "passive"))
      (node (ref "R20") (pin "2") (pinfunction "2_2") (pintype "passive"))
    )
    (net (code "47") (name "Net-(Q2-S)") (class "Default")
      (node (ref "C15") (pin "1") (pinfunction "1_1") (pintype "passive"))
      (node (ref "C16") (pin "1") (pinfunction "1_1") (pintype "passive"))
      (node (ref "C17") (pin "1") (pinfunction "1_1") (pintype "passive"))
      (node (ref "Q2") (pin "3") (pinfunction "S_3") (pintype "passive"))
      (node (ref "R20") (pin "1") (pinfunction "1_1") (pintype "passive"))
      (node (ref "R33") (pin "2") (pinfunction "2_2") (pintype "passive"))
      (node (ref "U16") (pin "4") (pinfunction "+_4") (pintype "passive"))
    )
    (net (code "48") (name "Net-(Q4-B)") (class "Default")
      (node (ref "Q4") (pin "2") (pinfunction "B_2") (pintype "passive"))
      (node (ref "R22") (pin "2") (pinfunction "2_2") (pintype "passive"))
    )
    (net (code "49") (name "Net-(Q4-C)") (class "Default")
      (node (ref "Q4") (pin "1") (pinfunction "C_1") (pintype "passive"))
      (node (ref "R24") (pin "1") (pinfunction "1_1") (pintype "passive"))
      (node (ref "R28") (pin "1") (pinfunction "1_1") (pintype "passive"))
    )
    (net (code "50") (name "Net-(Q5-B)") (class "Default")
      (node (ref "Q5") (pin "1") (pinfunction "B_1") (pintype "passive"))
      (node (ref "R24") (pin "2") (pinfunction "2_2") (pintype "passive"))
    )
    (net (code "51") (name "Net-(Q6-B)") (class "Default")
      (node (ref "Q6") (pin "2") (pinfunction "B_2") (pintype "passive"))
      (node (ref "R25") (pin "2") (pinfunction "2_2") (pintype "passive"))
    )
    (net (code "52") (name "Net-(Q6-C)") (class "Default")
      (node (ref "Q6") (pin "1") (pinfunction "C_1") (pintype "passive"))
      (node (ref "R26") (pin "2") (pinfunction "2_2") (pintype "passive"))
      (node (ref "R30") (pin "1") (pinfunction "1_1") (pintype "passive"))
    )
    (net (code "53") (name "Net-(Q7-B)") (class "Default")
      (node (ref "Q7") (pin "2") (pinfunction "B_2") (pintype "passive"))
      (node (ref "R26") (pin "1") (pinfunction "1_1") (pintype "passive"))
    )
    (net (code "54") (name "Net-(R5-BOT)") (class "Default")
      (node (ref "R11") (pin "1") (pinfunction "1_1") (pintype "passive"))
      (node (ref "R5") (pin "2") (pinfunction "BOT_2") (pintype "passive"))
    )
    (net (code "55") (name "Net-(R38-TAP)") (class "Default")
      (node (ref "R38") (pin "3") (pinfunction "TAP_3") (pintype "passive"))
      (node (ref "R39") (pin "2") (pinfunction "2_2") (pintype "passive"))
    )
    (net (code "56") (name "Net-(R42-TAP)") (class "Default")
      (node (ref "R37") (pin "2") (pinfunction "2_2") (pintype "passive"))
      (node (ref "R42") (pin "3") (pinfunction "TAP_3") (pintype "passive"))
    )
    (net (code "57") (name "Net-(U1-Cathode)") (class "Default")
      (node (ref "U1") (pin "2") (pinfunction "Cathode_2") (pintype "passive"))
      (node (ref "U5") (pin "1") (pinfunction "1OUT_1") (pintype "passive"))
    )
    (net (code "58") (name "Net-(U4-1IN+)") (class "Default")
      (node (ref "R8") (pin "1") (pinfunction "1_1") (pintype "passive"))
      (node (ref "U4") (pin "3") (pinfunction "1IN+_3") (pintype "passive"))
    )
    (net (code "59") (name "Net-(U4-1IN-)") (class "Default")
      (node (ref "C2") (pin "2") (pinfunction "2_2") (pintype "passive"))
      (node (ref "R4") (pin "1") (pinfunction "1_1") (pintype "passive"))
      (node (ref "U4") (pin "2") (pinfunction "1IN-_2") (pintype "passive"))
    )
    (net (code "60") (name "Net-(U4-2N+)") (class "Default")
      (node (ref "R14") (pin "1") (pinfunction "1_1") (pintype "passive"))
      (node (ref "U4") (pin "5") (pinfunction "2N+_5") (pintype "passive"))
    )
    (net (code "61") (name "Net-(U4-2N-)") (class "Default")
      (node (ref "R7") (pin "2") (pinfunction "2_2") (pintype "passive"))
      (node (ref "U4") (pin "6") (pinfunction "2N-_6") (pintype "passive"))
    )
    (net (code "62") (name "Net-(U5-2N+)") (class "Default")
      (node (ref "R10") (pin "1") (pinfunction "1_1") (pintype "passive"))
      (node (ref "U5") (pin "5") (pinfunction "2N+_5") (pintype "passive"))
    )
    (net (code "63") (name "Net-(U5-2N-)") (class "Default")
      (node (ref "R6") (pin "1") (pinfunction "1_1") (pintype "passive"))
      (node (ref "U5") (pin "6") (pinfunction "2N-_6") (pintype "passive"))
    )
    (net (code "64") (name "Net-(U9-Anode)") (class "Default")
      (node (ref "R13") (pin "2") (pinfunction "2_2") (pintype "passive"))
      (node (ref "U9") (pin "1") (pinfunction "Anode_1") (pintype "passive"))
    )
    (net (code "65") (name "Net-(U12-0V)") (class "Default")
      (node (ref "U12") (pin "4") (pinfunction "0V_4") (pintype "passive"))
      (node (ref "U16") (pin "2") (pinfunction "~_2") (pintype "passive"))
    )
    (net (code "66") (name "Net-(U12-25V)") (class "Default")
      (node (ref "U12") (pin "2") (pinfunction "25V_2") (pintype "passive"))
      (node (ref "U13") (pin "5") (pinfunction "O_5") (pintype "passive"))
    )
    (net (code "67") (name "Net-(U12-35V)") (class "Default")
      (node (ref "U12") (pin "1") (pinfunction "35V_1") (pintype "passive"))
      (node (ref "U14") (pin "5") (pinfunction "O_5") (pintype "passive"))
    )
    (net (code "68") (name "Net-(U13-C)") (class "Default")
      (node (ref "U13") (pin "2") (pinfunction "C_2") (pintype "passive"))
      (node (ref "U14") (pin "4") (pinfunction "I_4") (pintype "passive"))
    )
    (net (code "69") (name "Net-(U14-C)") (class "Default")
      (node (ref "U14") (pin "2") (pinfunction "C_2") (pintype "passive"))
      (node (ref "U16") (pin "3") (pinfunction "~_3") (pintype "passive"))
    )
    (net (code "70") (name "Net-(U19-Anode)") (class "Default")
      (node (ref "R29") (pin "2") (pinfunction "2_2") (pintype "passive"))
      (node (ref "U19") (pin "1") (pinfunction "Anode_1") (pintype "passive"))
    )
    (net (code "71") (name "Net-(U23-IN1+)") (class "Default")
      (node (ref "R43") (pin "1") (pinfunction "1_1") (pintype "passive"))
      (node (ref "U23") (pin "3") (pinfunction "IN1+_3") (pintype "passive"))
    )
    (net (code "72") (name "Net-(U23-IN1-)") (class "Default")
      (node (ref "R35") (pin "2") (pinfunction "2_2") (pintype "passive"))
      (node (ref "R39") (pin "1") (pinfunction "1_1") (pintype "passive"))
      (node (ref "U23") (pin "2") (pinfunction "IN1-_2") (pintype "passive"))
    )
    (net (code "73") (name "Net-(U23-IN2+)") (class "Default")
      (node (ref "R44") (pin "2") (pinfunction "2_2") (pintype "passive"))
      (node (ref "U23") (pin "5") (pinfunction "IN2+_5") (pintype "passive"))
    )
    (net (code "74") (name "Net-(U23-IN2-)") (class "Default")
      (node (ref "R36") (pin "2") (pinfunction "2_2") (pintype "passive"))
      (node (ref "R37") (pin "1") (pinfunction "1_1") (pintype "passive"))
      (node (ref "U23") (pin "6") (pinfunction "IN2-_6") (pintype "passive"))
    )
    (net (code "75") (name "Net-(U23-OUT1)") (class "Default")
      (node (ref "R40") (pin "2") (pinfunction "2_2") (pintype "passive"))
      (node (ref "U23") (pin "1") (pinfunction "OUT1_1") (pintype "passive"))
    )
    (net (code "76") (name "Net-(U23-OUT2)") (class "Default")
      (node (ref "R41") (pin "2") (pinfunction "2_2") (pintype "passive"))
      (node (ref "U23") (pin "7") (pinfunction "OUT2_7") (pintype "passive"))
    )
    (net (code "77") (name "unconnected-(U5-2OUT-Pad7)") (class "Default")
      (node (ref "U5") (pin "7") (pinfunction "2OUT_7") (pintype "passive"))
    )
  )
)
